# artik530_SOM.net
KiCad netlist of a schematic drawn in EAGLE
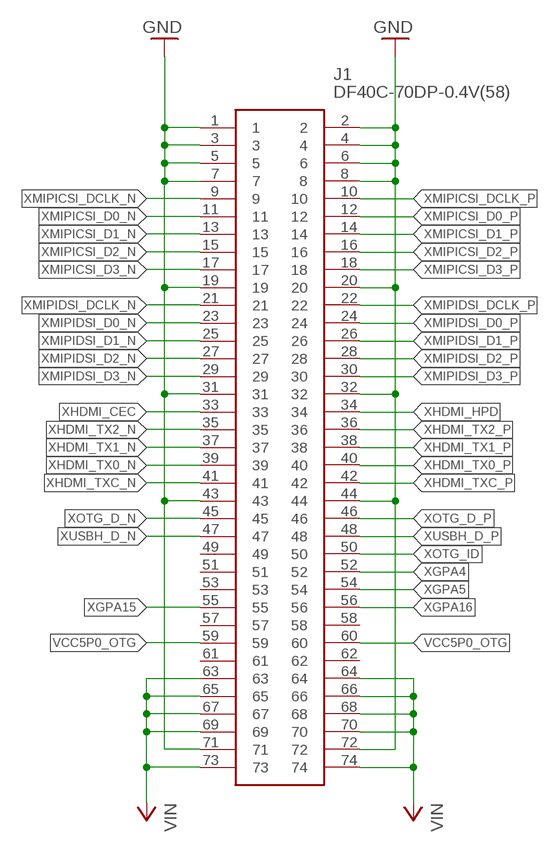
[diagram p0: schematic, sheet 1, part 1 of 2]
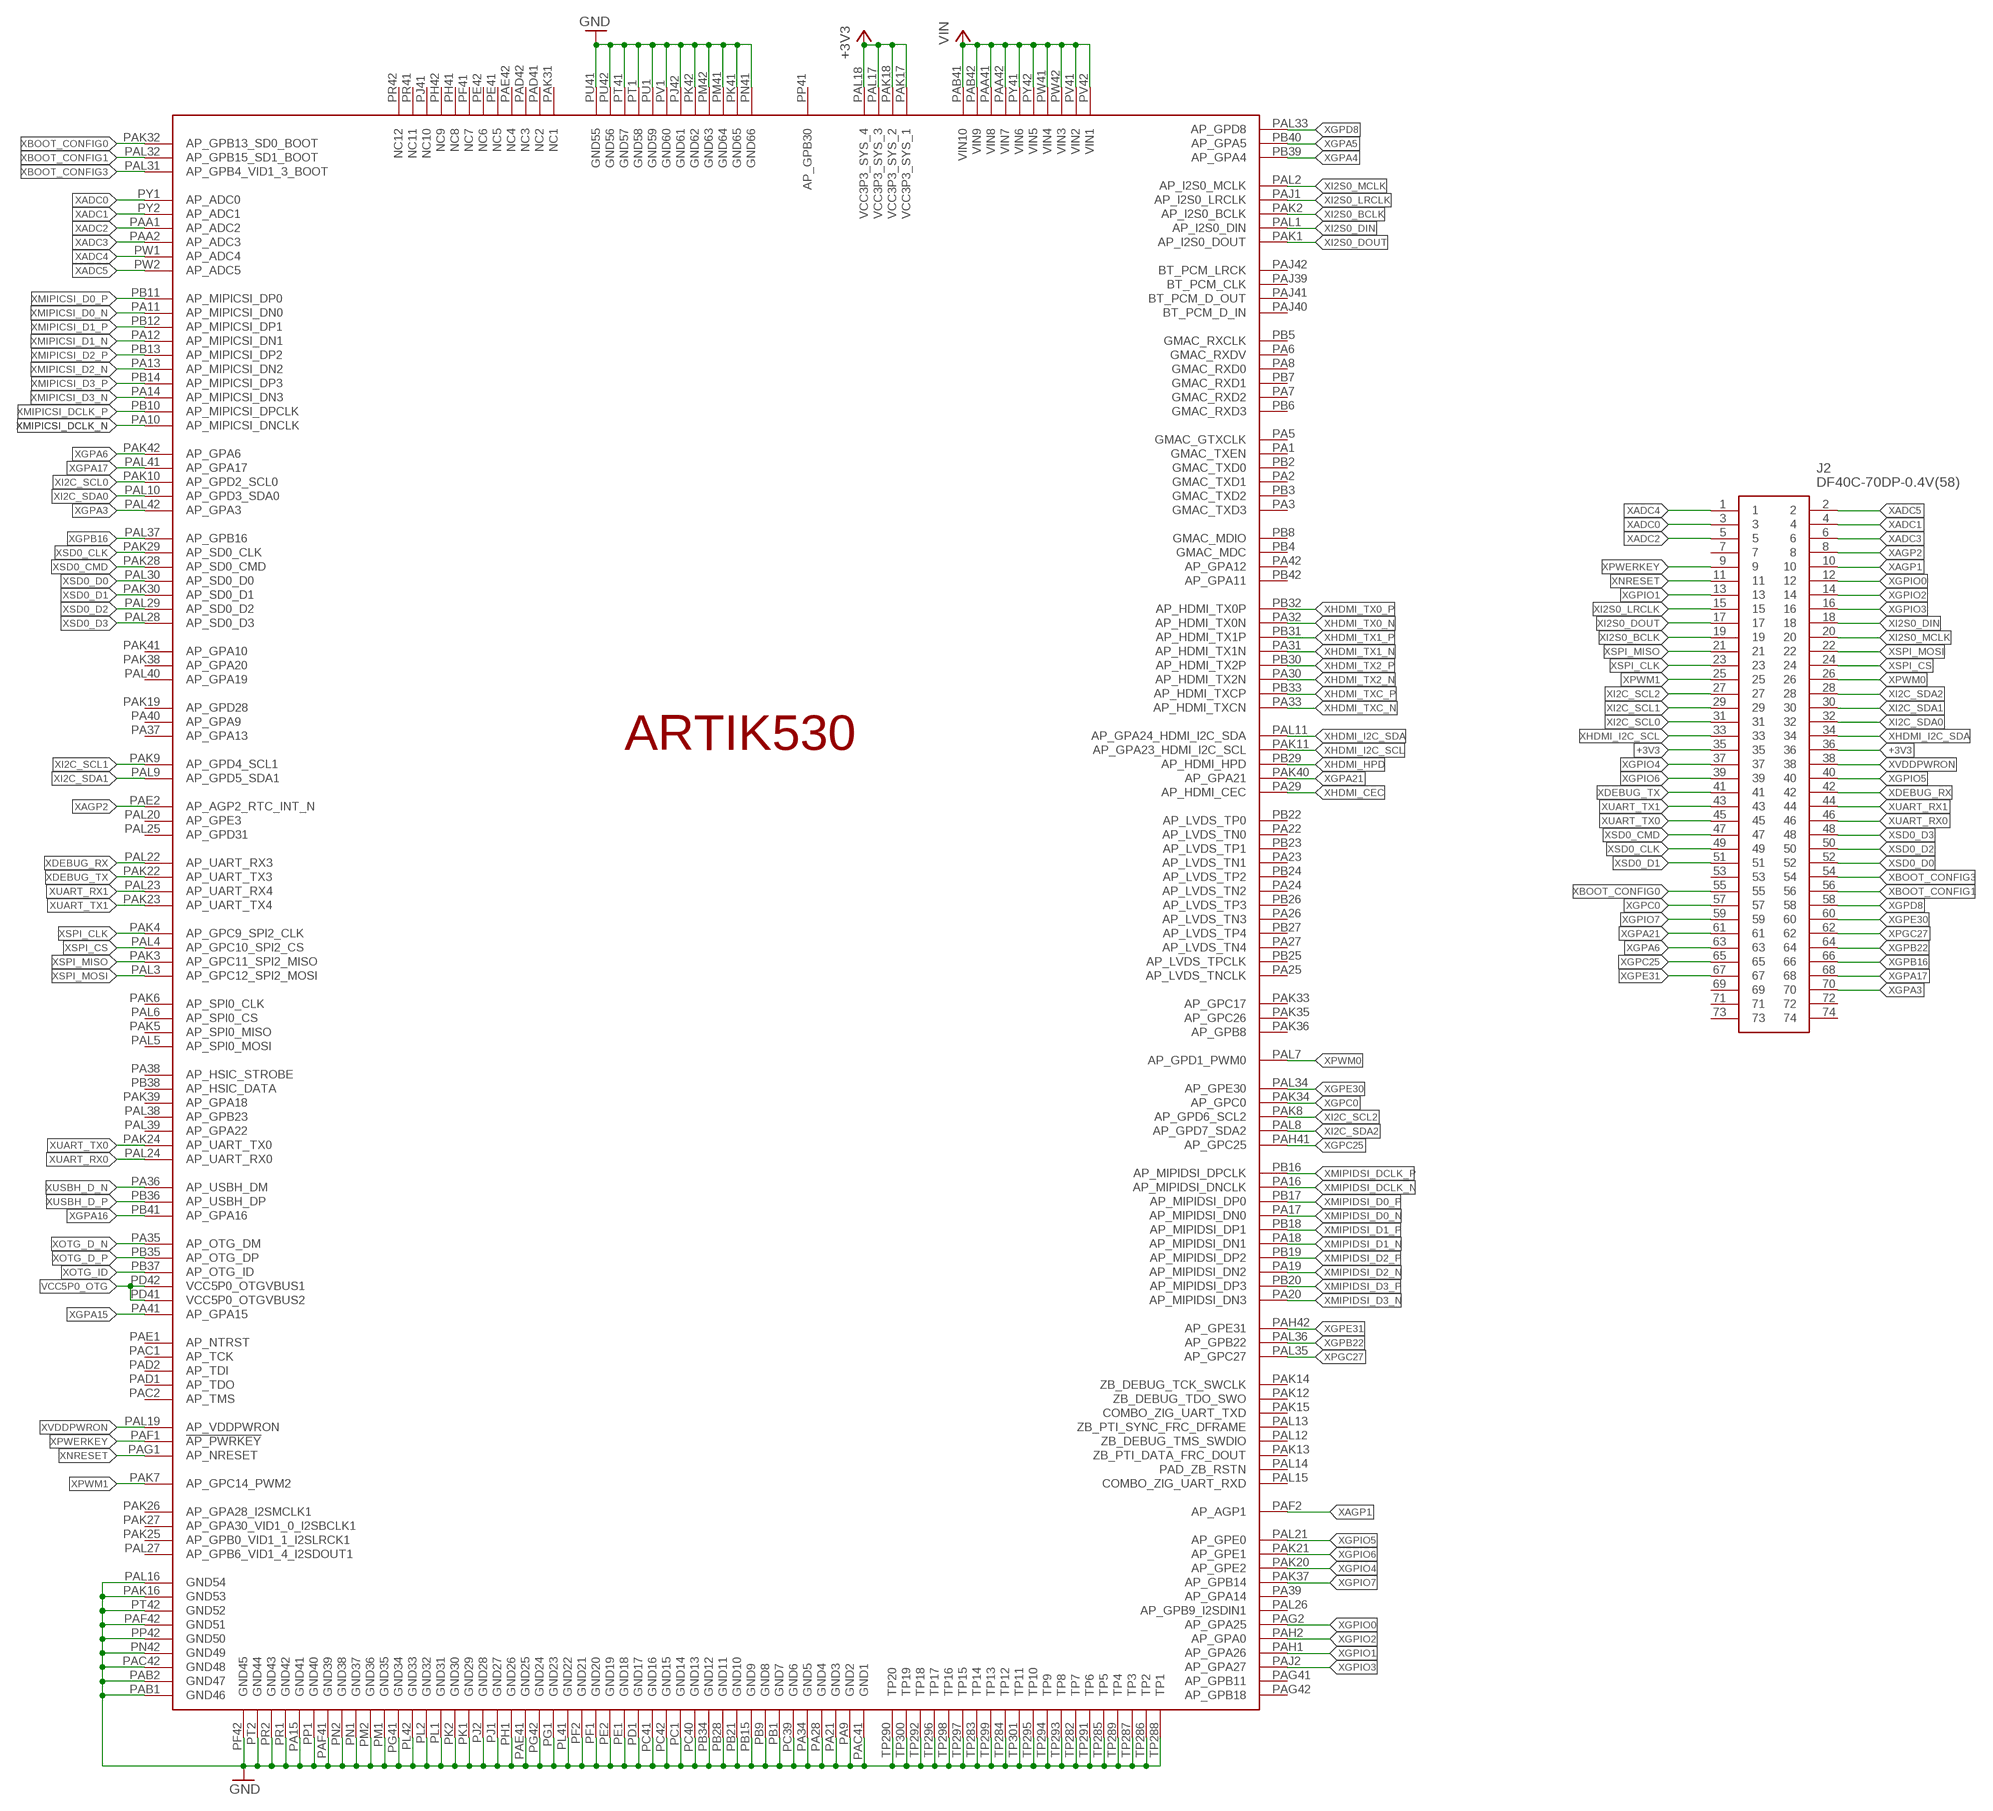
[diagram p1: schematic, sheet 1, part 2 of 2]

(export (version "E")
  (design (tool "Eeschema 10.0.6"))
  (components
    (comp (ref "J1")
      (value "DF40C-70DP-0.4V(58)")
      (footprint "eagle-import:DF40C70DP04V58")
      (fields
        (field (name "ARROW_PART_NUMBER") "DF40C-70DP-0.4V(51)")
        (field (name "RS_PART_NUMBER") "1664877")
      )
      (libsource (lib "eagle-import") (part "DF40C-70DP-0.4V(58)"))
    )
    (comp (ref "J2")
      (value "DF40C-70DP-0.4V(58)")
      (footprint "eagle-import:DF40C70DP04V58")
      (fields
        (field (name "ARROW_PART_NUMBER") "DF40C-70DP-0.4V(51)")
        (field (name "RS_PART_NUMBER") "1664877")
      )
      (libsource (lib "eagle-import") (part "DF40C-70DP-0.4V(58)"))
    )
    (comp (ref "U$1")
      (value "ARTIK530ARTIK530_SOM")
      (footprint "eagle-import:ARTIK5")
      (libsource (lib "eagle-import") (part "ARTIK530ARTIK530_SOM"))
    )
  )
  (nets
    (net (code "1") (name "+3V3") (class "Default")
      (node (ref "J2") (pin "35") (pinfunction "35_35") (pintype "bidirectional"))
      (node (ref "J2") (pin "36") (pinfunction "36_36") (pintype "bidirectional"))
      (node (ref "U$1") (pin "PAK17") (pinfunction "VCC3P3_SYS_1_PAK17") (pintype "bidirectional"))
      (node (ref "U$1") (pin "PAK18") (pinfunction "VCC3P3_SYS_2_PAK18") (pintype "bidirectional"))
      (node (ref "U$1") (pin "PAL17") (pinfunction "VCC3P3_SYS_3_PAL17") (pintype "bidirectional"))
      (node (ref "U$1") (pin "PAL18") (pinfunction "VCC3P3_SYS_4_PAL18") (pintype "bidirectional"))
    )
    (net (code "2") (name "GND") (class "Default")
      (node (ref "J1") (pin "1") (pinfunction "1_1") (pintype "bidirectional"))
      (node (ref "J1") (pin "19") (pinfunction "19_19") (pintype "bidirectional"))
      (node (ref "J1") (pin "2") (pinfunction "2_2") (pintype "bidirectional"))
      (node (ref "J1") (pin "20") (pinfunction "20_20") (pintype "bidirectional"))
      (node (ref "J1") (pin "3") (pinfunction "3_3") (pintype "bidirectional"))
      (node (ref "J1") (pin "31") (pinfunction "31_31") (pintype "bidirectional"))
      (node (ref "J1") (pin "32") (pinfunction "32_32") (pintype "bidirectional"))
      (node (ref "J1") (pin "4") (pinfunction "4_4") (pintype "bidirectional"))
      (node (ref "J1") (pin "43") (pinfunction "43_43") (pintype "bidirectional"))
      (node (ref "J1") (pin "44") (pinfunction "44_44") (pintype "bidirectional"))
      (node (ref "J1") (pin "5") (pinfunction "5_5") (pintype "bidirectional"))
      (node (ref "J1") (pin "6") (pinfunction "6_6") (pintype "bidirectional"))
      (node (ref "J1") (pin "7") (pinfunction "7_7") (pintype "bidirectional"))
      (node (ref "J1") (pin "71") (pinfunction "71_71") (pintype "bidirectional"))
      (node (ref "J1") (pin "72") (pinfunction "72_72") (pintype "bidirectional"))
      (node (ref "J1") (pin "8") (pinfunction "8_8") (pintype "bidirectional"))
      (node (ref "U$1") (pin "PA15") (pinfunction "GND41_PA15") (pintype "bidirectional"))
      (node (ref "U$1") (pin "PA21") (pinfunction "GND3_PA21") (pintype "bidirectional"))
      (node (ref "U$1") (pin "PA28") (pinfunction "GND4_PA28") (pintype "bidirectional"))
      (node (ref "U$1") (pin "PA34") (pinfunction "GND5_PA34") (pintype "bidirectional"))
      (node (ref "U$1") (pin "PA9") (pinfunction "GND2_PA9") (pintype "bidirectional"))
      (node (ref "U$1") (pin "PAB1") (pinfunction "GND46_PAB1") (pintype "bidirectional"))
      (node (ref "U$1") (pin "PAB2") (pinfunction "GND47_PAB2") (pintype "bidirectional"))
      (node (ref "U$1") (pin "PAC41") (pinfunction "GND1_PAC41") (pintype "bidirectional"))
      (node (ref "U$1") (pin "PAC42") (pinfunction "GND48_PAC42") (pintype "bidirectional"))
      (node (ref "U$1") (pin "PAE41") (pinfunction "GND25_PAE41") (pintype "bidirectional"))
      (node (ref "U$1") (pin "PAF41") (pinfunction "GND39_PAF41") (pintype "bidirectional"))
      (node (ref "U$1") (pin "PAF42") (pinfunction "GND51_PAF42") (pintype "bidirectional"))
      (node (ref "U$1") (pin "PAK16") (pinfunction "GND53_PAK16") (pintype "bidirectional"))
      (node (ref "U$1") (pin "PAL16") (pinfunction "GND54_PAL16") (pintype "bidirectional"))
      (node (ref "U$1") (pin "PB1") (pinfunction "GND7_PB1") (pintype "bidirectional"))
      (node (ref "U$1") (pin "PB15") (pinfunction "GND9_PB15") (pintype "bidirectional"))
      (node (ref "U$1") (pin "PB21") (pinfunction "GND10_PB21") (pintype "bidirectional"))
      (node (ref "U$1") (pin "PB28") (pinfunction "GND11_PB28") (pintype "bidirectional"))
      (node (ref "U$1") (pin "PB34") (pinfunction "GND12_PB34") (pintype "bidirectional"))
      (node (ref "U$1") (pin "PB9") (pinfunction "GND8_PB9") (pintype "bidirectional"))
      (node (ref "U$1") (pin "PC1") (pinfunction "GND14_PC1") (pintype "bidirectional"))
      (node (ref "U$1") (pin "PC39") (pinfunction "GND6_PC39") (pintype "bidirectional"))
      (node (ref "U$1") (pin "PC40") (pinfunction "GND13_PC40") (pintype "bidirectional"))
      (node (ref "U$1") (pin "PC41") (pinfunction "GND16_PC41") (pintype "bidirectional"))
      (node (ref "U$1") (pin "PC42") (pinfunction "GND15_PC42") (pintype "bidirectional"))
      (node (ref "U$1") (pin "PD1") (pinfunction "GND17_PD1") (pintype "bidirectional"))
      (node (ref "U$1") (pin "PE1") (pinfunction "GND18_PE1") (pintype "bidirectional"))
      (node (ref "U$1") (pin "PE2") (pinfunction "GND19_PE2") (pintype "bidirectional"))
      (node (ref "U$1") (pin "PF1") (pinfunction "GND20_PF1") (pintype "bidirectional"))
      (node (ref "U$1") (pin "PF2") (pinfunction "GND21_PF2") (pintype "bidirectional"))
      (node (ref "U$1") (pin "PF42") (pinfunction "GND45_PF42") (pintype "bidirectional"))
      (node (ref "U$1") (pin "PG1") (pinfunction "GND23_PG1") (pintype "bidirectional"))
      (node (ref "U$1") (pin "PG41") (pinfunction "GND34_PG41") (pintype "bidirectional"))
      (node (ref "U$1") (pin "PG42") (pinfunction "GND24_PG42") (pintype "bidirectional"))
      (node (ref "U$1") (pin "PH1") (pinfunction "GND26_PH1") (pintype "bidirectional"))
      (node (ref "U$1") (pin "PJ1") (pinfunction "GND27_PJ1") (pintype "bidirectional"))
      (node (ref "U$1") (pin "PJ2") (pinfunction "GND28_PJ2") (pintype "bidirectional"))
      (node (ref "U$1") (pin "PJ42") (pinfunction "GND61_PJ42") (pintype "bidirectional"))
      (node (ref "U$1") (pin "PK1") (pinfunction "GND29_PK1") (pintype "bidirectional"))
      (node (ref "U$1") (pin "PK2") (pinfunction "GND30_PK2") (pintype "bidirectional"))
      (node (ref "U$1") (pin "PK41") (pinfunction "GND65_PK41") (pintype "bidirectional"))
      (node (ref "U$1") (pin "PK42") (pinfunction "GND62_PK42") (pintype "bidirectional"))
      (node (ref "U$1") (pin "PL1") (pinfunction "GND31_PL1") (pintype "bidirectional"))
      (node (ref "U$1") (pin "PL2") (pinfunction "GND32_PL2") (pintype "bidirectional"))
      (node (ref "U$1") (pin "PL41") (pinfunction "GND22_PL41") (pintype "bidirectional"))
      (node (ref "U$1") (pin "PL42") (pinfunction "GND33_PL42") (pintype "bidirectional"))
      (node (ref "U$1") (pin "PM1") (pinfunction "GND35_PM1") (pintype "bidirectional"))
      (node (ref "U$1") (pin "PM2") (pinfunction "GND36_PM2") (pintype "bidirectional"))
      (node (ref "U$1") (pin "PM41") (pinfunction "GND64_PM41") (pintype "bidirectional"))
      (node (ref "U$1") (pin "PM42") (pinfunction "GND63_PM42") (pintype "bidirectional"))
      (node (ref "U$1") (pin "PN1") (pinfunction "GND37_PN1") (pintype "bidirectional"))
      (node (ref "U$1") (pin "PN2") (pinfunction "GND38_PN2") (pintype "bidirectional"))
      (node (ref "U$1") (pin "PN41") (pinfunction "GND66_PN41") (pintype "bidirectional"))
      (node (ref "U$1") (pin "PN42") (pinfunction "GND49_PN42") (pintype "bidirectional"))
      (node (ref "U$1") (pin "PP1") (pinfunction "GND40_PP1") (pintype "bidirectional"))
      (node (ref "U$1") (pin "PP42") (pinfunction "GND50_PP42") (pintype "bidirectional"))
      (node (ref "U$1") (pin "PR1") (pinfunction "GND42_PR1") (pintype "bidirectional"))
      (node (ref "U$1") (pin "PR2") (pinfunction "GND43_PR2") (pintype "bidirectional"))
      (node (ref "U$1") (pin "PT1") (pinfunction "GND58_PT1") (pintype "bidirectional"))
      (node (ref "U$1") (pin "PT2") (pinfunction "GND44_PT2") (pintype "bidirectional"))
      (node (ref "U$1") (pin "PT41") (pinfunction "GND57_PT41") (pintype "bidirectional"))
      (node (ref "U$1") (pin "PT42") (pinfunction "GND52_PT42") (pintype "bidirectional"))
      (node (ref "U$1") (pin "PU1") (pinfunction "GND59_PU1") (pintype "bidirectional"))
      (node (ref "U$1") (pin "PU41") (pinfunction "GND55_PU41") (pintype "bidirectional"))
      (node (ref "U$1") (pin "PU42") (pinfunction "GND56_PU42") (pintype "bidirectional"))
      (node (ref "U$1") (pin "PV1") (pinfunction "GND60_PV1") (pintype "bidirectional"))
      (node (ref "U$1") (pin "TP282") (pinfunction "TP7_TP282") (pintype "bidirectional"))
      (node (ref "U$1") (pin "TP283") (pinfunction "TP14_TP283") (pintype "bidirectional"))
      (node (ref "U$1") (pin "TP284") (pinfunction "TP12_TP284") (pintype "bidirectional"))
      (node (ref "U$1") (pin "TP285") (pinfunction "TP5_TP285") (pintype "bidirectional"))
      (node (ref "U$1") (pin "TP286") (pinfunction "TP2_TP286") (pintype "bidirectional"))
      (node (ref "U$1") (pin "TP287") (pinfunction "TP3_TP287") (pintype "bidirectional"))
      (node (ref "U$1") (pin "TP288") (pinfunction "TP1_TP288") (pintype "bidirectional"))
      (node (ref "U$1") (pin "TP289") (pinfunction "TP4_TP289") (pintype "bidirectional"))
      (node (ref "U$1") (pin "TP290") (pinfunction "TP20_TP290") (pintype "bidirectional"))
      (node (ref "U$1") (pin "TP291") (pinfunction "TP6_TP291") (pintype "bidirectional"))
      (node (ref "U$1") (pin "TP292") (pinfunction "TP18_TP292") (pintype "bidirectional"))
      (node (ref "U$1") (pin "TP293") (pinfunction "TP8_TP293") (pintype "bidirectional"))
      (node (ref "U$1") (pin "TP294") (pinfunction "TP9_TP294") (pintype "bidirectional"))
      (node (ref "U$1") (pin "TP295") (pinfunction "TP10_TP295") (pintype "bidirectional"))
      (node (ref "U$1") (pin "TP296") (pinfunction "TP17_TP296") (pintype "bidirectional"))
      (node (ref "U$1") (pin "TP297") (pinfunction "TP15_TP297") (pintype "bidirectional"))
      (node (ref "U$1") (pin "TP298") (pinfunction "TP16_TP298") (pintype "bidirectional"))
      (node (ref "U$1") (pin "TP299") (pinfunction "TP13_TP299") (pintype "bidirectional"))
      (node (ref "U$1") (pin "TP300") (pinfunction "TP19_TP300") (pintype "bidirectional"))
      (node (ref "U$1") (pin "TP301") (pinfunction "TP11_TP301") (pintype "bidirectional"))
    )
    (net (code "3") (name "VCC5P0_OTG") (class "Default")
      (node (ref "J1") (pin "59") (pinfunction "59_59") (pintype "bidirectional"))
      (node (ref "J1") (pin "60") (pinfunction "60_60") (pintype "bidirectional"))
      (node (ref "U$1") (pin "PD41") (pinfunction "VCC5P0_OTGVBUS2_PD41") (pintype "bidirectional"))
      (node (ref "U$1") (pin "PD42") (pinfunction "VCC5P0_OTGVBUS1_PD42") (pintype "bidirectional"))
    )
    (net (code "4") (name "VIN") (class "Default")
      (node (ref "J1") (pin "63") (pinfunction "63_63") (pintype "bidirectional"))
      (node (ref "J1") (pin "64") (pinfunction "64_64") (pintype "bidirectional"))
      (node (ref "J1") (pin "65") (pinfunction "65_65") (pintype "bidirectional"))
      (node (ref "J1") (pin "66") (pinfunction "66_66") (pintype "bidirectional"))
      (node (ref "J1") (pin "67") (pinfunction "67_67") (pintype "bidirectional"))
      (node (ref "J1") (pin "68") (pinfunction "68_68") (pintype "bidirectional"))
      (node (ref "J1") (pin "69") (pinfunction "69_69") (pintype "bidirectional"))
      (node (ref "J1") (pin "70") (pinfunction "70_70") (pintype "bidirectional"))
      (node (ref "J1") (pin "73") (pinfunction "73_73") (pintype "bidirectional"))
      (node (ref "J1") (pin "74") (pinfunction "74_74") (pintype "bidirectional"))
      (node (ref "U$1") (pin "PAA41") (pinfunction "VIN8_PAA41") (pintype "bidirectional"))
      (node (ref "U$1") (pin "PAA42") (pinfunction "VIN7_PAA42") (pintype "bidirectional"))
      (node (ref "U$1") (pin "PAB41") (pinfunction "VIN10_PAB41") (pintype "bidirectional"))
      (node (ref "U$1") (pin "PAB42") (pinfunction "VIN9_PAB42") (pintype "bidirectional"))
      (node (ref "U$1") (pin "PV41") (pinfunction "VIN2_PV41") (pintype "bidirectional"))
      (node (ref "U$1") (pin "PV42") (pinfunction "VIN1_PV42") (pintype "bidirectional"))
      (node (ref "U$1") (pin "PW41") (pinfunction "VIN4_PW41") (pintype "bidirectional"))
      (node (ref "U$1") (pin "PW42") (pinfunction "VIN3_PW42") (pintype "bidirectional"))
      (node (ref "U$1") (pin "PY41") (pinfunction "VIN6_PY41") (pintype "bidirectional"))
      (node (ref "U$1") (pin "PY42") (pinfunction "VIN5_PY42") (pintype "bidirectional"))
    )
    (net (code "5") (name "XADC0") (class "Default")
      (node (ref "J2") (pin "3") (pinfunction "3_3") (pintype "bidirectional"))
      (node (ref "U$1") (pin "PY1") (pinfunction "AP_ADC0_PY1") (pintype "bidirectional"))
    )
    (net (code "6") (name "XADC1") (class "Default")
      (node (ref "J2") (pin "4") (pinfunction "4_4") (pintype "bidirectional"))
      (node (ref "U$1") (pin "PY2") (pinfunction "AP_ADC1_PY2") (pintype "bidirectional"))
    )
    (net (code "7") (name "XADC2") (class "Default")
      (node (ref "J2") (pin "5") (pinfunction "5_5") (pintype "bidirectional"))
      (node (ref "U$1") (pin "PAA1") (pinfunction "AP_ADC2_PAA1") (pintype "bidirectional"))
    )
    (net (code "8") (name "XADC3") (class "Default")
      (node (ref "J2") (pin "6") (pinfunction "6_6") (pintype "bidirectional"))
      (node (ref "U$1") (pin "PAA2") (pinfunction "AP_ADC3_PAA2") (pintype "bidirectional"))
    )
    (net (code "9") (name "XADC4") (class "Default")
      (node (ref "J2") (pin "1") (pinfunction "1_1") (pintype "bidirectional"))
      (node (ref "U$1") (pin "PW1") (pinfunction "AP_ADC4_PW1") (pintype "bidirectional"))
    )
    (net (code "10") (name "XADC5") (class "Default")
      (node (ref "J2") (pin "2") (pinfunction "2_2") (pintype "bidirectional"))
      (node (ref "U$1") (pin "PW2") (pinfunction "AP_ADC5_PW2") (pintype "bidirectional"))
    )
    (net (code "11") (name "XAGP1") (class "Default")
      (node (ref "J2") (pin "10") (pinfunction "10_10") (pintype "bidirectional"))
      (node (ref "U$1") (pin "PAF2") (pinfunction "AP_AGP1_PAF2") (pintype "bidirectional"))
    )
    (net (code "12") (name "XAGP2") (class "Default")
      (node (ref "J2") (pin "8") (pinfunction "8_8") (pintype "bidirectional"))
      (node (ref "U$1") (pin "PAE2") (pinfunction "AP_AGP2_RTC_INT_N_PAE2") (pintype "bidirectional"))
    )
    (net (code "13") (name "XBOOT_CONFIG0") (class "Default")
      (node (ref "J2") (pin "55") (pinfunction "55_55") (pintype "bidirectional"))
      (node (ref "U$1") (pin "PAK32") (pinfunction "AP_GPB13_SD0_BOOT_PAK32") (pintype "bidirectional"))
    )
    (net (code "14") (name "XBOOT_CONFIG1") (class "Default")
      (node (ref "J2") (pin "56") (pinfunction "56_56") (pintype "bidirectional"))
      (node (ref "U$1") (pin "PAL32") (pinfunction "AP_GPB15_SD1_BOOT_PAL32") (pintype "bidirectional"))
    )
    (net (code "15") (name "XBOOT_CONFIG3") (class "Default")
      (node (ref "J2") (pin "54") (pinfunction "54_54") (pintype "bidirectional"))
      (node (ref "U$1") (pin "PAL31") (pinfunction "AP_GPB4_VID1_3_BOOT_PAL31") (pintype "bidirectional"))
    )
    (net (code "16") (name "XDEBUG_RX") (class "Default")
      (node (ref "J2") (pin "42") (pinfunction "42_42") (pintype "bidirectional"))
      (node (ref "U$1") (pin "PAL22") (pinfunction "AP_UART_RX3_PAL22") (pintype "bidirectional"))
    )
    (net (code "17") (name "XDEBUG_TX") (class "Default")
      (node (ref "J2") (pin "41") (pinfunction "41_41") (pintype "bidirectional"))
      (node (ref "U$1") (pin "PAK22") (pinfunction "AP_UART_TX3_PAK22") (pintype "bidirectional"))
    )
    (net (code "18") (name "XGPA3") (class "Default")
      (node (ref "J2") (pin "70") (pinfunction "70_70") (pintype "bidirectional"))
      (node (ref "U$1") (pin "PAL42") (pinfunction "AP_GPA3_PAL42") (pintype "bidirectional"))
    )
    (net (code "19") (name "XGPA4") (class "Default")
      (node (ref "J1") (pin "52") (pinfunction "52_52") (pintype "bidirectional"))
      (node (ref "U$1") (pin "PB39") (pinfunction "AP_GPA4_PB39") (pintype "bidirectional"))
    )
    (net (code "20") (name "XGPA5") (class "Default")
      (node (ref "J1") (pin "54") (pinfunction "54_54") (pintype "bidirectional"))
      (node (ref "U$1") (pin "PB40") (pinfunction "AP_GPA5_PB40") (pintype "bidirectional"))
    )
    (net (code "21") (name "XGPA6") (class "Default")
      (node (ref "J2") (pin "63") (pinfunction "63_63") (pintype "bidirectional"))
      (node (ref "U$1") (pin "PAK42") (pinfunction "AP_GPA6_PAK42") (pintype "bidirectional"))
    )
    (net (code "22") (name "XGPA15") (class "Default")
      (node (ref "J1") (pin "55") (pinfunction "55_55") (pintype "bidirectional"))
      (node (ref "U$1") (pin "PA41") (pinfunction "AP_GPA15_PA41") (pintype "bidirectional"))
    )
    (net (code "23") (name "XGPA16") (class "Default")
      (node (ref "J1") (pin "56") (pinfunction "56_56") (pintype "bidirectional"))
      (node (ref "U$1") (pin "PB41") (pinfunction "AP_GPA16_PB41") (pintype "bidirectional"))
    )
    (net (code "24") (name "XGPA17") (class "Default")
      (node (ref "J2") (pin "68") (pinfunction "68_68") (pintype "bidirectional"))
      (node (ref "U$1") (pin "PAL41") (pinfunction "AP_GPA17_PAL41") (pintype "bidirectional"))
    )
    (net (code "25") (name "XGPA21") (class "Default")
      (node (ref "J2") (pin "61") (pinfunction "61_61") (pintype "bidirectional"))
      (node (ref "U$1") (pin "PAK40") (pinfunction "AP_GPA21_PAK40") (pintype "bidirectional"))
    )
    (net (code "26") (name "XGPB16") (class "Default")
      (node (ref "J2") (pin "66") (pinfunction "66_66") (pintype "bidirectional"))
      (node (ref "U$1") (pin "PAL37") (pinfunction "AP_GPB16_PAL37") (pintype "bidirectional"))
    )
    (net (code "27") (name "XGPB22") (class "Default")
      (node (ref "J2") (pin "64") (pinfunction "64_64") (pintype "bidirectional"))
      (node (ref "U$1") (pin "PAL36") (pinfunction "AP_GPB22_PAL36") (pintype "bidirectional"))
    )
    (net (code "28") (name "XGPC0") (class "Default")
      (node (ref "J2") (pin "57") (pinfunction "57_57") (pintype "bidirectional"))
      (node (ref "U$1") (pin "PAK34") (pinfunction "AP_GPC0_PAK34") (pintype "bidirectional"))
    )
    (net (code "29") (name "XGPC25") (class "Default")
      (node (ref "J2") (pin "65") (pinfunction "65_65") (pintype "bidirectional"))
      (node (ref "U$1") (pin "PAH41") (pinfunction "AP_GPC25_PAH41") (pintype "bidirectional"))
    )
    (net (code "30") (name "XGPD8") (class "Default")
      (node (ref "J2") (pin "58") (pinfunction "58_58") (pintype "bidirectional"))
      (node (ref "U$1") (pin "PAL33") (pinfunction "AP_GPD8_PAL33") (pintype "bidirectional"))
    )
    (net (code "31") (name "XGPE30") (class "Default")
      (node (ref "J2") (pin "60") (pinfunction "60_60") (pintype "bidirectional"))
      (node (ref "U$1") (pin "PAL34") (pinfunction "AP_GPE30_PAL34") (pintype "bidirectional"))
    )
    (net (code "32") (name "XGPE31") (class "Default")
      (node (ref "J2") (pin "67") (pinfunction "67_67") (pintype "bidirectional"))
      (node (ref "U$1") (pin "PAH42") (pinfunction "AP_GPE31_PAH42") (pintype "bidirectional"))
    )
    (net (code "33") (name "XGPIO0") (class "Default")
      (node (ref "J2") (pin "12") (pinfunction "12_12") (pintype "bidirectional"))
      (node (ref "U$1") (pin "PAG2") (pinfunction "AP_GPA25_PAG2") (pintype "bidirectional"))
    )
    (net (code "34") (name "XGPIO1") (class "Default")
      (node (ref "J2") (pin "13") (pinfunction "13_13") (pintype "bidirectional"))
      (node (ref "U$1") (pin "PAH1") (pinfunction "AP_GPA26_PAH1") (pintype "bidirectional"))
    )
    (net (code "35") (name "XGPIO2") (class "Default")
      (node (ref "J2") (pin "14") (pinfunction "14_14") (pintype "bidirectional"))
      (node (ref "U$1") (pin "PAH2") (pinfunction "AP_GPA0_PAH2") (pintype "bidirectional"))
    )
    (net (code "36") (name "XGPIO3") (class "Default")
      (node (ref "J2") (pin "16") (pinfunction "16_16") (pintype "bidirectional"))
      (node (ref "U$1") (pin "PAJ2") (pinfunction "AP_GPA27_PAJ2") (pintype "bidirectional"))
    )
    (net (code "37") (name "XGPIO4") (class "Default")
      (node (ref "J2") (pin "37") (pinfunction "37_37") (pintype "bidirectional"))
      (node (ref "U$1") (pin "PAK20") (pinfunction "AP_GPE2_PAK20") (pintype "bidirectional"))
    )
    (net (code "38") (name "XGPIO5") (class "Default")
      (node (ref "J2") (pin "40") (pinfunction "40_40") (pintype "bidirectional"))
      (node (ref "U$1") (pin "PAL21") (pinfunction "AP_GPE0_PAL21") (pintype "bidirectional"))
    )
    (net (code "39") (name "XGPIO6") (class "Default")
      (node (ref "J2") (pin "39") (pinfunction "39_39") (pintype "bidirectional"))
      (node (ref "U$1") (pin "PAK21") (pinfunction "AP_GPE1_PAK21") (pintype "bidirectional"))
    )
    (net (code "40") (name "XGPIO7") (class "Default")
      (node (ref "J2") (pin "59") (pinfunction "59_59") (pintype "bidirectional"))
      (node (ref "U$1") (pin "PAK37") (pinfunction "AP_GPB14_PAK37") (pintype "bidirectional"))
    )
    (net (code "41") (name "XHDMI_CEC") (class "Default")
      (node (ref "J1") (pin "33") (pinfunction "33_33") (pintype "bidirectional"))
      (node (ref "U$1") (pin "PA29") (pinfunction "AP_HDMI_CEC_PA29") (pintype "bidirectional"))
    )
    (net (code "42") (name "XHDMI_HPD") (class "Default")
      (node (ref "J1") (pin "34") (pinfunction "34_34") (pintype "bidirectional"))
      (node (ref "U$1") (pin "PB29") (pinfunction "AP_HDMI_HPD_PB29") (pintype "bidirectional"))
    )
    (net (code "43") (name "XHDMI_I2C_SCL") (class "Default")
      (node (ref "J2") (pin "33") (pinfunction "33_33") (pintype "bidirectional"))
      (node (ref "U$1") (pin "PAK11") (pinfunction "AP_GPA23_HDMI_I2C_SCL_PAK11") (pintype "bidirectional"))
    )
    (net (code "44") (name "XHDMI_I2C_SDA") (class "Default")
      (node (ref "J2") (pin "34") (pinfunction "34_34") (pintype "bidirectional"))
      (node (ref "U$1") (pin "PAL11") (pinfunction "AP_GPA24_HDMI_I2C_SDA_PAL11") (pintype "bidirectional"))
    )
    (net (code "45") (name "XHDMI_TX0_N") (class "Default")
      (node (ref "J1") (pin "39") (pinfunction "39_39") (pintype "bidirectional"))
      (node (ref "U$1") (pin "PA32") (pinfunction "AP_HDMI_TX0N_PA32") (pintype "bidirectional"))
    )
    (net (code "46") (name "XHDMI_TX0_P") (class "Default")
      (node (ref "J1") (pin "40") (pinfunction "40_40") (pintype "bidirectional"))
      (node (ref "U$1") (pin "PB32") (pinfunction "AP_HDMI_TX0P_PB32") (pintype "bidirectional"))
    )
    (net (code "47") (name "XHDMI_TX1_N") (class "Default")
      (node (ref "J1") (pin "37") (pinfunction "37_37") (pintype "bidirectional"))
      (node (ref "U$1") (pin "PA31") (pinfunction "AP_HDMI_TX1N_PA31") (pintype "bidirectional"))
    )
    (net (code "48") (name "XHDMI_TX1_P") (class "Default")
      (node (ref "J1") (pin "38") (pinfunction "38_38") (pintype "bidirectional"))
      (node (ref "U$1") (pin "PB31") (pinfunction "AP_HDMI_TX1P_PB31") (pintype "bidirectional"))
    )
    (net (code "49") (name "XHDMI_TX2_N") (class "Default")
      (node (ref "J1") (pin "35") (pinfunction "35_35") (pintype "bidirectional"))
      (node (ref "U$1") (pin "PA30") (pinfunction "AP_HDMI_TX2N_PA30") (pintype "bidirectional"))
    )
    (net (code "50") (name "XHDMI_TX2_P") (class "Default")
      (node (ref "J1") (pin "36") (pinfunction "36_36") (pintype "bidirectional"))
      (node (ref "U$1") (pin "PB30") (pinfunction "AP_HDMI_TX2P_PB30") (pintype "bidirectional"))
    )
    (net (code "51") (name "XHDMI_TXC_N") (class "Default")
      (node (ref "J1") (pin "41") (pinfunction "41_41") (pintype "bidirectional"))
      (node (ref "U$1") (pin "PA33") (pinfunction "AP_HDMI_TXCN_PA33") (pintype "bidirectional"))
    )
    (net (code "52") (name "XHDMI_TXC_P") (class "Default")
      (node (ref "J1") (pin "42") (pinfunction "42_42") (pintype "bidirectional"))
      (node (ref "U$1") (pin "PB33") (pinfunction "AP_HDMI_TXCP_PB33") (pintype "bidirectional"))
    )
    (net (code "53") (name "XI2C_SCL0") (class "Default")
      (node (ref "J2") (pin "31") (pinfunction "31_31") (pintype "bidirectional"))
      (node (ref "U$1") (pin "PAK10") (pinfunction "AP_GPD2_SCL0_PAK10") (pintype "bidirectional"))
    )
    (net (code "54") (name "XI2C_SCL1") (class "Default")
      (node (ref "J2") (pin "29") (pinfunction "29_29") (pintype "bidirectional"))
      (node (ref "U$1") (pin "PAK9") (pinfunction "AP_GPD4_SCL1_PAK9") (pintype "bidirectional"))
    )
    (net (code "55") (name "XI2C_SCL2") (class "Default")
      (node (ref "J2") (pin "27") (pinfunction "27_27") (pintype "bidirectional"))
      (node (ref "U$1") (pin "PAK8") (pinfunction "AP_GPD6_SCL2_PAK8") (pintype "bidirectional"))
    )
    (net (code "56") (name "XI2C_SDA0") (class "Default")
      (node (ref "J2") (pin "32") (pinfunction "32_32") (pintype "bidirectional"))
      (node (ref "U$1") (pin "PAL10") (pinfunction "AP_GPD3_SDA0_PAL10") (pintype "bidirectional"))
    )
    (net (code "57") (name "XI2C_SDA1") (class "Default")
      (node (ref "J2") (pin "30") (pinfunction "30_30") (pintype "bidirectional"))
      (node (ref "U$1") (pin "PAL9") (pinfunction "AP_GPD5_SDA1_PAL9") (pintype "bidirectional"))
    )
    (net (code "58") (name "XI2C_SDA2") (class "Default")
      (node (ref "J2") (pin "28") (pinfunction "28_28") (pintype "bidirectional"))
      (node (ref "U$1") (pin "PAL8") (pinfunction "AP_GPD7_SDA2_PAL8") (pintype "bidirectional"))
    )
    (net (code "59") (name "XI2S0_BCLK") (class "Default")
      (node (ref "J2") (pin "19") (pinfunction "19_19") (pintype "bidirectional"))
      (node (ref "U$1") (pin "PAK2") (pinfunction "AP_I2S0_BCLK_PAK2") (pintype "bidirectional"))
    )
    (net (code "60") (name "XI2S0_DIN") (class "Default")
      (node (ref "J2") (pin "18") (pinfunction "18_18") (pintype "bidirectional"))
      (node (ref "U$1") (pin "PAL1") (pinfunction "AP_I2S0_DIN_PAL1") (pintype "bidirectional"))
    )
    (net (code "61") (name "XI2S0_DOUT") (class "Default")
      (node (ref "J2") (pin "17") (pinfunction "17_17") (pintype "bidirectional"))
      (node (ref "U$1") (pin "PAK1") (pinfunction "AP_I2S0_DOUT_PAK1") (pintype "bidirectional"))
    )
    (net (code "62") (name "XI2S0_LRCLK") (class "Default")
      (node (ref "J2") (pin "15") (pinfunction "15_15") (pintype "bidirectional"))
      (node (ref "U$1") (pin "PAJ1") (pinfunction "AP_I2S0_LRCLK_PAJ1") (pintype "bidirectional"))
    )
    (net (code "63") (name "XI2S0_MCLK") (class "Default")
      (node (ref "J2") (pin "20") (pinfunction "20_20") (pintype "bidirectional"))
      (node (ref "U$1") (pin "PAL2") (pinfunction "AP_I2S0_MCLK_PAL2") (pintype "bidirectional"))
    )
    (net (code "64") (name "XMIPICSI_D0_N") (class "Default")
      (node (ref "J1") (pin "11") (pinfunction "11_11") (pintype "bidirectional"))
      (node (ref "U$1") (pin "PA11") (pinfunction "AP_MIPICSI_DN0_PA11") (pintype "bidirectional"))
    )
    (net (code "65") (name "XMIPICSI_D0_P") (class "Default")
      (node (ref "J1") (pin "12") (pinfunction "12_12") (pintype "bidirectional"))
      (node (ref "U$1") (pin "PB11") (pinfunction "AP_MIPICSI_DP0_PB11") (pintype "bidirectional"))
    )
    (net (code "66") (name "XMIPICSI_D1_N") (class "Default")
      (node (ref "J1") (pin "13") (pinfunction "13_13") (pintype "bidirectional"))
      (node (ref "U$1") (pin "PA12") (pinfunction "AP_MIPICSI_DN1_PA12") (pintype "bidirectional"))
    )
    (net (code "67") (name "XMIPICSI_D1_P") (class "Default")
      (node (ref "J1") (pin "14") (pinfunction "14_14") (pintype "bidirectional"))
      (node (ref "U$1") (pin "PB12") (pinfunction "AP_MIPICSI_DP1_PB12") (pintype "bidirectional"))
    )
    (net (code "68") (name "XMIPICSI_D2_N") (class "Default")
      (node (ref "J1") (pin "15") (pinfunction "15_15") (pintype "bidirectional"))
      (node (ref "U$1") (pin "PA13") (pinfunction "AP_MIPICSI_DN2_PA13") (pintype "bidirectional"))
    )
    (net (code "69") (name "XMIPICSI_D2_P") (class "Default")
      (node (ref "J1") (pin "16") (pinfunction "16_16") (pintype "bidirectional"))
      (node (ref "U$1") (pin "PB13") (pinfunction "AP_MIPICSI_DP2_PB13") (pintype "bidirectional"))
    )
    (net (code "70") (name "XMIPICSI_D3_N") (class "Default")
      (node (ref "J1") (pin "17") (pinfunction "17_17") (pintype "bidirectional"))
      (node (ref "U$1") (pin "PA14") (pinfunction "AP_MIPICSI_DN3_PA14") (pintype "bidirectional"))
    )
    (net (code "71") (name "XMIPICSI_D3_P") (class "Default")
      (node (ref "J1") (pin "18") (pinfunction "18_18") (pintype "bidirectional"))
      (node (ref "U$1") (pin "PB14") (pinfunction "AP_MIPICSI_DP3_PB14") (pintype "bidirectional"))
    )
    (net (code "72") (name "XMIPICSI_DCLK_N") (class "Default")
      (node (ref "J1") (pin "9") (pinfunction "9_9") (pintype "bidirectional"))
      (node (ref "U$1") (pin "PA10") (pinfunction "AP_MIPICSI_DNCLK_PA10") (pintype "bidirectional"))
    )
    (net (code "73") (name "XMIPICSI_DCLK_P") (class "Default")
      (node (ref "J1") (pin "10") (pinfunction "10_10") (pintype "bidirectional"))
      (node (ref "U$1") (pin "PB10") (pinfunction "AP_MIPICSI_DPCLK_PB10") (pintype "bidirectional"))
    )
    (net (code "74") (name "XMIPIDSI_D0_N") (class "Default")
      (node (ref "J1") (pin "23") (pinfunction "23_23") (pintype "bidirectional"))
      (node (ref "U$1") (pin "PA17") (pinfunction "AP_MIPIDSI_DN0_PA17") (pintype "bidirectional"))
    )
    (net (code "75") (name "XMIPIDSI_D0_P") (class "Default")
      (node (ref "J1") (pin "24") (pinfunction "24_24") (pintype "bidirectional"))
      (node (ref "U$1") (pin "PB17") (pinfunction "AP_MIPIDSI_DP0_PB17") (pintype "bidirectional"))
    )
    (net (code "76") (name "XMIPIDSI_D1_N") (class "Default")
      (node (ref "J1") (pin "25") (pinfunction "25_25") (pintype "bidirectional"))
      (node (ref "U$1") (pin "PA18") (pinfunction "AP_MIPIDSI_DN1_PA18") (pintype "bidirectional"))
    )
    (net (code "77") (name "XMIPIDSI_D1_P") (class "Default")
      (node (ref "J1") (pin "26") (pinfunction "26_26") (pintype "bidirectional"))
      (node (ref "U$1") (pin "PB18") (pinfunction "AP_MIPIDSI_DP1_PB18") (pintype "bidirectional"))
    )
    (net (code "78") (name "XMIPIDSI_D2_N") (class "Default")
      (node (ref "J1") (pin "27") (pinfunction "27_27") (pintype "bidirectional"))
      (node (ref "U$1") (pin "PA19") (pinfunction "AP_MIPIDSI_DN2_PA19") (pintype "bidirectional"))
    )
    (net (code "79") (name "XMIPIDSI_D2_P") (class "Default")
      (node (ref "J1") (pin "28") (pinfunction "28_28") (pintype "bidirectional"))
      (node (ref "U$1") (pin "PB19") (pinfunction "AP_MIPIDSI_DP2_PB19") (pintype "bidirectional"))
    )
    (net (code "80") (name "XMIPIDSI_D3_N") (class "Default")
      (node (ref "J1") (pin "29") (pinfunction "29_29") (pintype "bidirectional"))
      (node (ref "U$1") (pin "PA20") (pinfunction "AP_MIPIDSI_DN3_PA20") (pintype "bidirectional"))
    )
    (net (code "81") (name "XMIPIDSI_D3_P") (class "Default")
      (node (ref "J1") (pin "30") (pinfunction "30_30") (pintype "bidirectional"))
      (node (ref "U$1") (pin "PB20") (pinfunction "AP_MIPIDSI_DP3_PB20") (pintype "bidirectional"))
    )
    (net (code "82") (name "XMIPIDSI_DCLK_N") (class "Default")
      (node (ref "J1") (pin "21") (pinfunction "21_21") (pintype "bidirectional"))
      (node (ref "U$1") (pin "PA16") (pinfunction "AP_MIPIDSI_DNCLK_PA16") (pintype "bidirectional"))
    )
    (net (code "83") (name "XMIPIDSI_DCLK_P") (class "Default")
      (node (ref "J1") (pin "22") (pinfunction "22_22") (pintype "bidirectional"))
      (node (ref "U$1") (pin "PB16") (pinfunction "AP_MIPIDSI_DPCLK_PB16") (pintype "bidirectional"))
    )
    (net (code "84") (name "XNRESET") (class "Default")
      (node (ref "J2") (pin "11") (pinfunction "11_11") (pintype "bidirectional"))
      (node (ref "U$1") (pin "PAG1") (pinfunction "AP_NRESET_PAG1") (pintype "bidirectional"))
    )
    (net (code "85") (name "XOTG_D_N") (class "Default")
      (node (ref "J1") (pin "45") (pinfunction "45_45") (pintype "bidirectional"))
      (node (ref "U$1") (pin "PA35") (pinfunction "AP_OTG_DM_PA35") (pintype "bidirectional"))
    )
    (net (code "86") (name "XOTG_D_P") (class "Default")
      (node (ref "J1") (pin "46") (pinfunction "46_46") (pintype "bidirectional"))
      (node (ref "U$1") (pin "PB35") (pinfunction "AP_OTG_DP_PB35") (pintype "bidirectional"))
    )
    (net (code "87") (name "XOTG_ID") (class "Default")
      (node (ref "J1") (pin "50") (pinfunction "50_50") (pintype "bidirectional"))
      (node (ref "U$1") (pin "PB37") (pinfunction "AP_OTG_ID_PB37") (pintype "bidirectional"))
    )
    (net (code "88") (name "XPGC27") (class "Default")
      (node (ref "J2") (pin "62") (pinfunction "62_62") (pintype "bidirectional"))
      (node (ref "U$1") (pin "PAL35") (pinfunction "AP_GPC27_PAL35") (pintype "bidirectional"))
    )
    (net (code "89") (name "XPWERKEY") (class "Default")
      (node (ref "J2") (pin "9") (pinfunction "9_9") (pintype "bidirectional"))
      (node (ref "U$1") (pin "PAF1") (pinfunction "~{AP_PWRKEY}_PAF1") (pintype "bidirectional"))
    )
    (net (code "90") (name "XPWM0") (class "Default")
      (node (ref "J2") (pin "26") (pinfunction "26_26") (pintype "bidirectional"))
      (node (ref "U$1") (pin "PAL7") (pinfunction "AP_GPD1_PWM0_PAL7") (pintype "bidirectional"))
    )
    (net (code "91") (name "XPWM1") (class "Default")
      (node (ref "J2") (pin "25") (pinfunction "25_25") (pintype "bidirectional"))
      (node (ref "U$1") (pin "PAK7") (pinfunction "AP_GPC14_PWM2_PAK7") (pintype "bidirectional"))
    )
    (net (code "92") (name "XSD0_CLK") (class "Default")
      (node (ref "J2") (pin "49") (pinfunction "49_49") (pintype "bidirectional"))
      (node (ref "U$1") (pin "PAK29") (pinfunction "AP_SD0_CLK_PAK29") (pintype "bidirectional"))
    )
    (net (code "93") (name "XSD0_CMD") (class "Default")
      (node (ref "J2") (pin "47") (pinfunction "47_47") (pintype "bidirectional"))
      (node (ref "U$1") (pin "PAK28") (pinfunction "AP_SD0_CMD_PAK28") (pintype "bidirectional"))
    )
    (net (code "94") (name "XSD0_D0") (class "Default")
      (node (ref "J2") (pin "52") (pinfunction "52_52") (pintype "bidirectional"))
      (node (ref "U$1") (pin "PAL30") (pinfunction "AP_SD0_D0_PAL30") (pintype "bidirectional"))
    )
    (net (code "95") (name "XSD0_D1") (class "Default")
      (node (ref "J2") (pin "51") (pinfunction "51_51") (pintype "bidirectional"))
      (node (ref "U$1") (pin "PAK30") (pinfunction "AP_SD0_D1_PAK30") (pintype "bidirectional"))
    )
    (net (code "96") (name "XSD0_D2") (class "Default")
      (node (ref "J2") (pin "50") (pinfunction "50_50") (pintype "bidirectional"))
      (node (ref "U$1") (pin "PAL29") (pinfunction "AP_SD0_D2_PAL29") (pintype "bidirectional"))
    )
    (net (code "97") (name "XSD0_D3") (class "Default")
      (node (ref "J2") (pin "48") (pinfunction "48_48") (pintype "bidirectional"))
      (node (ref "U$1") (pin "PAL28") (pinfunction "AP_SD0_D3_PAL28") (pintype "bidirectional"))
    )
    (net (code "98") (name "XSPI_CLK") (class "Default")
      (node (ref "J2") (pin "23") (pinfunction "23_23") (pintype "bidirectional"))
      (node (ref "U$1") (pin "PAK4") (pinfunction "AP_GPC9_SPI2_CLK_PAK4") (pintype "bidirectional"))
    )
    (net (code "99") (name "XSPI_CS") (class "Default")
      (node (ref "J2") (pin "24") (pinfunction "24_24") (pintype "bidirectional"))
      (node (ref "U$1") (pin "PAL4") (pinfunction "AP_GPC10_SPI2_CS_PAL4") (pintype "bidirectional"))
    )
    (net (code "100") (name "XSPI_MISO") (class "Default")
      (node (ref "J2") (pin "21") (pinfunction "21_21") (pintype "bidirectional"))
      (node (ref "U$1") (pin "PAK3") (pinfunction "AP_GPC11_SPI2_MISO_PAK3") (pintype "bidirectional"))
    )
    (net (code "101") (name "XSPI_MOSI") (class "Default")
      (node (ref "J2") (pin "22") (pinfunction "22_22") (pintype "bidirectional"))
      (node (ref "U$1") (pin "PAL3") (pinfunction "AP_GPC12_SPI2_MOSI_PAL3") (pintype "bidirectional"))
    )
    (net (code "102") (name "XUART_RX0") (class "Default")
      (node (ref "J2") (pin "46") (pinfunction "46_46") (pintype "bidirectional"))
      (node (ref "U$1") (pin "PAL24") (pinfunction "AP_UART_RX0_PAL24") (pintype "bidirectional"))
    )
    (net (code "103") (name "XUART_RX1") (class "Default")
      (node (ref "J2") (pin "44") (pinfunction "44_44") (pintype "bidirectional"))
      (node (ref "U$1") (pin "PAL23") (pinfunction "AP_UART_RX4_PAL23") (pintype "bidirectional"))
    )
    (net (code "104") (name "XUART_TX0") (class "Default")
      (node (ref "J2") (pin "45") (pinfunction "45_45") (pintype "bidirectional"))
      (node (ref "U$1") (pin "PAK24") (pinfunction "AP_UART_TX0_PAK24") (pintype "bidirectional"))
    )
    (net (code "105") (name "XUART_TX1") (class "Default")
      (node (ref "J2") (pin "43") (pinfunction "43_43") (pintype "bidirectional"))
      (node (ref "U$1") (pin "PAK23") (pinfunction "AP_UART_TX4_PAK23") (pintype "bidirectional"))
    )
    (net (code "106") (name "XUSBH_D_N") (class "Default")
      (node (ref "J1") (pin "47") (pinfunction "47_47") (pintype "bidirectional"))
      (node (ref "U$1") (pin "PA36") (pinfunction "AP_USBH_DM_PA36") (pintype "bidirectional"))
    )
    (net (code "107") (name "XUSBH_D_P") (class "Default")
      (node (ref "J1") (pin "48") (pinfunction "48_48") (pintype "bidirectional"))
      (node (ref "U$1") (pin "PB36") (pinfunction "AP_USBH_DP_PB36") (pintype "bidirectional"))
    )
    (net (code "108") (name "XVDDPWRON") (class "Default")
      (node (ref "J2") (pin "38") (pinfunction "38_38") (pintype "bidirectional"))
      (node (ref "U$1") (pin "PAL19") (pinfunction "AP_VDDPWRON_PAL19") (pintype "bidirectional"))
    )
    (net (code "109") (name "unconnected-(J1-Pad49)") (class "Default")
      (node (ref "J1") (pin "49") (pinfunction "49_49") (pintype "bidirectional"))
    )
    (net (code "110") (name "unconnected-(J1-Pad51)") (class "Default")
      (node (ref "J1") (pin "51") (pinfunction "51_51") (pintype "bidirectional"))
    )
    (net (code "111") (name "unconnected-(J1-Pad53)") (class "Default")
      (node (ref "J1") (pin "53") (pinfunction "53_53") (pintype "bidirectional"))
    )
    (net (code "112") (name "unconnected-(J1-Pad57)") (class "Default")
      (node (ref "J1") (pin "57") (pinfunction "57_57") (pintype "bidirectional"))
    )
    (net (code "113") (name "unconnected-(J1-Pad58)") (class "Default")
      (node (ref "J1") (pin "58") (pinfunction "58_58") (pintype "bidirectional"))
    )
    (net (code "114") (name "unconnected-(J1-Pad61)") (class "Default")
      (node (ref "J1") (pin "61") (pinfunction "61_61") (pintype "bidirectional"))
    )
    (net (code "115") (name "unconnected-(J1-Pad62)") (class "Default")
      (node (ref "J1") (pin "62") (pinfunction "62_62") (pintype "bidirectional"))
    )
    (net (code "116") (name "unconnected-(J2-Pad7)") (class "Default")
      (node (ref "J2") (pin "7") (pinfunction "7_7") (pintype "bidirectional"))
    )
    (net (code "117") (name "unconnected-(J2-Pad53)") (class "Default")
      (node (ref "J2") (pin "53") (pinfunction "53_53") (pintype "bidirectional"))
    )
    (net (code "118") (name "unconnected-(J2-Pad69)") (class "Default")
      (node (ref "J2") (pin "69") (pinfunction "69_69") (pintype "bidirectional"))
    )
    (net (code "119") (name "unconnected-(J2-Pad71)") (class "Default")
      (node (ref "J2") (pin "71") (pinfunction "71_71") (pintype "bidirectional"))
    )
    (net (code "120") (name "unconnected-(J2-Pad72)") (class "Default")
      (node (ref "J2") (pin "72") (pinfunction "72_72") (pintype "bidirectional"))
    )
    (net (code "121") (name "unconnected-(J2-Pad73)") (class "Default")
      (node (ref "J2") (pin "73") (pinfunction "73_73") (pintype "bidirectional"))
    )
    (net (code "122") (name "unconnected-(J2-Pad74)") (class "Default")
      (node (ref "J2") (pin "74") (pinfunction "74_74") (pintype "bidirectional"))
    )
    (net (code "123") (name "unconnected-(U$1-AP_GPA9-PadPA40)") (class "Default")
      (node (ref "U$1") (pin "PA40") (pinfunction "AP_GPA9_PA40") (pintype "bidirectional"))
    )
    (net (code "124") (name "unconnected-(U$1-AP_GPA10-PadPAK41)") (class "Default")
      (node (ref "U$1") (pin "PAK41") (pinfunction "AP_GPA10_PAK41") (pintype "bidirectional"))
    )
    (net (code "125") (name "unconnected-(U$1-AP_GPA11-PadPB42)") (class "Default")
      (node (ref "U$1") (pin "PB42") (pinfunction "AP_GPA11_PB42") (pintype "bidirectional"))
    )
    (net (code "126") (name "unconnected-(U$1-AP_GPA12-PadPA42)") (class "Default")
      (node (ref "U$1") (pin "PA42") (pinfunction "AP_GPA12_PA42") (pintype "bidirectional"))
    )
    (net (code "127") (name "unconnected-(U$1-AP_GPA13-PadPA37)") (class "Default")
      (node (ref "U$1") (pin "PA37") (pinfunction "AP_GPA13_PA37") (pintype "bidirectional"))
    )
    (net (code "128") (name "unconnected-(U$1-AP_GPA14-PadPA39)") (class "Default")
      (node (ref "U$1") (pin "PA39") (pinfunction "AP_GPA14_PA39") (pintype "bidirectional"))
    )
    (net (code "129") (name "unconnected-(U$1-AP_GPA18-PadPAK39)") (class "Default")
      (node (ref "U$1") (pin "PAK39") (pinfunction "AP_GPA18_PAK39") (pintype "bidirectional"))
    )
    (net (code "130") (name "unconnected-(U$1-AP_GPA19-PadPAL40)") (class "Default")
      (node (ref "U$1") (pin "PAL40") (pinfunction "AP_GPA19_PAL40") (pintype "bidirectional"))
    )
    (net (code "131") (name "unconnected-(U$1-AP_GPA20-PadPAK38)") (class "Default")
      (node (ref "U$1") (pin "PAK38") (pinfunction "AP_GPA20_PAK38") (pintype "bidirectional"))
    )
    (net (code "132") (name "unconnected-(U$1-AP_GPA22-PadPAL39)") (class "Default")
      (node (ref "U$1") (pin "PAL39") (pinfunction "AP_GPA22_PAL39") (pintype "bidirectional"))
    )
    (net (code "133") (name "unconnected-(U$1-AP_GPA28_I2SMCLK1-PadPAK26)") (class "Default")
      (node (ref "U$1") (pin "PAK26") (pinfunction "AP_GPA28_I2SMCLK1_PAK26") (pintype "bidirectional"))
    )
    (net (code "134") (name "unconnected-(U$1-AP_GPA30_VID1_0_I2SBCLK1-PadPAK27)") (class "Default")
      (node (ref "U$1") (pin "PAK27") (pinfunction "AP_GPA30_VID1_0_I2SBCLK1_PAK27") (pintype "bidirectional"))
    )
    (net (code "135") (name "unconnected-(U$1-AP_GPB0_VID1_1_I2SLRCK1-PadPAK25)") (class "Default")
      (node (ref "U$1") (pin "PAK25") (pinfunction "AP_GPB0_VID1_1_I2SLRCK1_PAK25") (pintype "bidirectional"))
    )
    (net (code "136") (name "unconnected-(U$1-AP_GPB6_VID1_4_I2SDOUT1-PadPAL27)") (class "Default")
      (node (ref "U$1") (pin "PAL27") (pinfunction "AP_GPB6_VID1_4_I2SDOUT1_PAL27") (pintype "bidirectional"))
    )
    (net (code "137") (name "unconnected-(U$1-AP_GPB8-PadPAK36)") (class "Default")
      (node (ref "U$1") (pin "PAK36") (pinfunction "AP_GPB8_PAK36") (pintype "bidirectional"))
    )
    (net (code "138") (name "unconnected-(U$1-AP_GPB9_I2SDIN1-PadPAL26)") (class "Default")
      (node (ref "U$1") (pin "PAL26") (pinfunction "AP_GPB9_I2SDIN1_PAL26") (pintype "bidirectional"))
    )
    (net (code "139") (name "unconnected-(U$1-AP_GPB11-PadPAG41)") (class "Default")
      (node (ref "U$1") (pin "PAG41") (pinfunction "AP_GPB11_PAG41") (pintype "bidirectional"))
    )
    (net (code "140") (name "unconnected-(U$1-AP_GPB18-PadPAG42)") (class "Default")
      (node (ref "U$1") (pin "PAG42") (pinfunction "AP_GPB18_PAG42") (pintype "bidirectional"))
    )
    (net (code "141") (name "unconnected-(U$1-AP_GPB23-PadPAL38)") (class "Default")
      (node (ref "U$1") (pin "PAL38") (pinfunction "AP_GPB23_PAL38") (pintype "bidirectional"))
    )
    (net (code "142") (name "unconnected-(U$1-AP_GPB30-PadPP41)") (class "Default")
      (node (ref "U$1") (pin "PP41") (pinfunction "AP_GPB30_PP41") (pintype "bidirectional"))
    )
    (net (code "143") (name "unconnected-(U$1-AP_GPC17-PadPAK33)") (class "Default")
      (node (ref "U$1") (pin "PAK33") (pinfunction "AP_GPC17_PAK33") (pintype "bidirectional"))
    )
    (net (code "144") (name "unconnected-(U$1-AP_GPC26-PadPAK35)") (class "Default")
      (node (ref "U$1") (pin "PAK35") (pinfunction "AP_GPC26_PAK35") (pintype "bidirectional"))
    )
    (net (code "145") (name "unconnected-(U$1-AP_GPD28-PadPAK19)") (class "Default")
      (node (ref "U$1") (pin "PAK19") (pinfunction "AP_GPD28_PAK19") (pintype "bidirectional"))
    )
    (net (code "146") (name "unconnected-(U$1-AP_GPD31-PadPAL25)") (class "Default")
      (node (ref "U$1") (pin "PAL25") (pinfunction "AP_GPD31_PAL25") (pintype "bidirectional"))
    )
    (net (code "147") (name "unconnected-(U$1-AP_GPE3-PadPAL20)") (class "Default")
      (node (ref "U$1") (pin "PAL20") (pinfunction "AP_GPE3_PAL20") (pintype "bidirectional"))
    )
    (net (code "148") (name "unconnected-(U$1-AP_HSIC_DATA-PadPB38)") (class "Default")
      (node (ref "U$1") (pin "PB38") (pinfunction "AP_HSIC_DATA_PB38") (pintype "bidirectional"))
    )
    (net (code "149") (name "unconnected-(U$1-AP_HSIC_STROBE-PadPA38)") (class "Default")
      (node (ref "U$1") (pin "PA38") (pinfunction "AP_HSIC_STROBE_PA38") (pintype "bidirectional"))
    )
    (net (code "150") (name "unconnected-(U$1-AP_LVDS_TN0-PadPA22)") (class "Default")
      (node (ref "U$1") (pin "PA22") (pinfunction "AP_LVDS_TN0_PA22") (pintype "bidirectional"))
    )
    (net (code "151") (name "unconnected-(U$1-AP_LVDS_TN1-PadPA23)") (class "Default")
      (node (ref "U$1") (pin "PA23") (pinfunction "AP_LVDS_TN1_PA23") (pintype "bidirectional"))
    )
    (net (code "152") (name "unconnected-(U$1-AP_LVDS_TN2-PadPA24)") (class "Default")
      (node (ref "U$1") (pin "PA24") (pinfunction "AP_LVDS_TN2_PA24") (pintype "bidirectional"))
    )
    (net (code "153") (name "unconnected-(U$1-AP_LVDS_TN3-PadPA26)") (class "Default")
      (node (ref "U$1") (pin "PA26") (pinfunction "AP_LVDS_TN3_PA26") (pintype "bidirectional"))
    )
    (net (code "154") (name "unconnected-(U$1-AP_LVDS_TN4-PadPA27)") (class "Default")
      (node (ref "U$1") (pin "PA27") (pinfunction "AP_LVDS_TN4_PA27") (pintype "bidirectional"))
    )
    (net (code "155") (name "unconnected-(U$1-AP_LVDS_TNCLK-PadPA25)") (class "Default")
      (node (ref "U$1") (pin "PA25") (pinfunction "AP_LVDS_TNCLK_PA25") (pintype "bidirectional"))
    )
    (net (code "156") (name "unconnected-(U$1-AP_LVDS_TP0-PadPB22)") (class "Default")
      (node (ref "U$1") (pin "PB22") (pinfunction "AP_LVDS_TP0_PB22") (pintype "bidirectional"))
    )
    (net (code "157") (name "unconnected-(U$1-AP_LVDS_TP1-PadPB23)") (class "Default")
      (node (ref "U$1") (pin "PB23") (pinfunction "AP_LVDS_TP1_PB23") (pintype "bidirectional"))
    )
    (net (code "158") (name "unconnected-(U$1-AP_LVDS_TP2-PadPB24)") (class "Default")
      (node (ref "U$1") (pin "PB24") (pinfunction "AP_LVDS_TP2_PB24") (pintype "bidirectional"))
    )
    (net (code "159") (name "unconnected-(U$1-AP_LVDS_TP3-PadPB26)") (class "Default")
      (node (ref "U$1") (pin "PB26") (pinfunction "AP_LVDS_TP3_PB26") (pintype "bidirectional"))
    )
    (net (code "160") (name "unconnected-(U$1-AP_LVDS_TP4-PadPB27)") (class "Default")
      (node (ref "U$1") (pin "PB27") (pinfunction "AP_LVDS_TP4_PB27") (pintype "bidirectional"))
    )
    (net (code "161") (name "unconnected-(U$1-AP_LVDS_TPCLK-PadPB25)") (class "Default")
      (node (ref "U$1") (pin "PB25") (pinfunction "AP_LVDS_TPCLK_PB25") (pintype "bidirectional"))
    )
    (net (code "162") (name "unconnected-(U$1-AP_NTRST-PadPAE1)") (class "Default")
      (node (ref "U$1") (pin "PAE1") (pinfunction "AP_NTRST_PAE1") (pintype "bidirectional"))
    )
    (net (code "163") (name "unconnected-(U$1-AP_SPI0_CLK-PadPAK6)") (class "Default")
      (node (ref "U$1") (pin "PAK6") (pinfunction "AP_SPI0_CLK_PAK6") (pintype "bidirectional"))
    )
    (net (code "164") (name "unconnected-(U$1-AP_SPI0_CS-PadPAL6)") (class "Default")
      (node (ref "U$1") (pin "PAL6") (pinfunction "AP_SPI0_CS_PAL6") (pintype "bidirectional"))
    )
    (net (code "165") (name "unconnected-(U$1-AP_SPI0_MISO-PadPAK5)") (class "Default")
      (node (ref "U$1") (pin "PAK5") (pinfunction "AP_SPI0_MISO_PAK5") (pintype "bidirectional"))
    )
    (net (code "166") (name "unconnected-(U$1-AP_SPI0_MOSI-PadPAL5)") (class "Default")
      (node (ref "U$1") (pin "PAL5") (pinfunction "AP_SPI0_MOSI_PAL5") (pintype "bidirectional"))
    )
    (net (code "167") (name "unconnected-(U$1-AP_TCK-PadPAC1)") (class "Default")
      (node (ref "U$1") (pin "PAC1") (pinfunction "AP_TCK_PAC1") (pintype "bidirectional"))
    )
    (net (code "168") (name "unconnected-(U$1-AP_TDI-PadPAD2)") (class "Default")
      (node (ref "U$1") (pin "PAD2") (pinfunction "AP_TDI_PAD2") (pintype "bidirectional"))
    )
    (net (code "169") (name "unconnected-(U$1-AP_TDO-PadPAD1)") (class "Default")
      (node (ref "U$1") (pin "PAD1") (pinfunction "AP_TDO_PAD1") (pintype "bidirectional"))
    )
    (net (code "170") (name "unconnected-(U$1-AP_TMS-PadPAC2)") (class "Default")
      (node (ref "U$1") (pin "PAC2") (pinfunction "AP_TMS_PAC2") (pintype "bidirectional"))
    )
    (net (code "171") (name "unconnected-(U$1-BT_PCM_CLK-PadPAJ39)") (class "Default")
      (node (ref "U$1") (pin "PAJ39") (pinfunction "BT_PCM_CLK_PAJ39") (pintype "bidirectional"))
    )
    (net (code "172") (name "unconnected-(U$1-BT_PCM_D_IN-PadPAJ40)") (class "Default")
      (node (ref "U$1") (pin "PAJ40") (pinfunction "BT_PCM_D_IN_PAJ40") (pintype "bidirectional"))
    )
    (net (code "173") (name "unconnected-(U$1-BT_PCM_D_OUT-PadPAJ41)") (class "Default")
      (node (ref "U$1") (pin "PAJ41") (pinfunction "BT_PCM_D_OUT_PAJ41") (pintype "bidirectional"))
    )
    (net (code "174") (name "unconnected-(U$1-BT_PCM_LRCK-PadPAJ42)") (class "Default")
      (node (ref "U$1") (pin "PAJ42") (pinfunction "BT_PCM_LRCK_PAJ42") (pintype "bidirectional"))
    )
    (net (code "175") (name "unconnected-(U$1-COMBO_ZIG_UART_RXD-PadPAL15)") (class "Default")
      (node (ref "U$1") (pin "PAL15") (pinfunction "COMBO_ZIG_UART_RXD_PAL15") (pintype "bidirectional"))
    )
    (net (code "176") (name "unconnected-(U$1-COMBO_ZIG_UART_TXD-PadPAK15)") (class "Default")
      (node (ref "U$1") (pin "PAK15") (pinfunction "COMBO_ZIG_UART_TXD_PAK15") (pintype "bidirectional"))
    )
    (net (code "177") (name "unconnected-(U$1-GMAC_GTXCLK-PadPA5)") (class "Default")
      (node (ref "U$1") (pin "PA5") (pinfunction "GMAC_GTXCLK_PA5") (pintype "bidirectional"))
    )
    (net (code "178") (name "unconnected-(U$1-GMAC_MDC-PadPB4)") (class "Default")
      (node (ref "U$1") (pin "PB4") (pinfunction "GMAC_MDC_PB4") (pintype "bidirectional"))
    )
    (net (code "179") (name "unconnected-(U$1-GMAC_MDIO-PadPB8)") (class "Default")
      (node (ref "U$1") (pin "PB8") (pinfunction "GMAC_MDIO_PB8") (pintype "bidirectional"))
    )
    (net (code "180") (name "unconnected-(U$1-GMAC_RXCLK-PadPB5)") (class "Default")
      (node (ref "U$1") (pin "PB5") (pinfunction "GMAC_RXCLK_PB5") (pintype "bidirectional"))
    )
    (net (code "181") (name "unconnected-(U$1-GMAC_RXD0-PadPA8)") (class "Default")
      (node (ref "U$1") (pin "PA8") (pinfunction "GMAC_RXD0_PA8") (pintype "bidirectional"))
    )
    (net (code "182") (name "unconnected-(U$1-GMAC_RXD1-PadPB7)") (class "Default")
      (node (ref "U$1") (pin "PB7") (pinfunction "GMAC_RXD1_PB7") (pintype "bidirectional"))
    )
    (net (code "183") (name "unconnected-(U$1-GMAC_RXD2-PadPA7)") (class "Default")
      (node (ref "U$1") (pin "PA7") (pinfunction "GMAC_RXD2_PA7") (pintype "bidirectional"))
    )
    (net (code "184") (name "unconnected-(U$1-GMAC_RXD3-PadPB6)") (class "Default")
      (node (ref "U$1") (pin "PB6") (pinfunction "GMAC_RXD3_PB6") (pintype "bidirectional"))
    )
    (net (code "185") (name "unconnected-(U$1-GMAC_RXDV-PadPA6)") (class "Default")
      (node (ref "U$1") (pin "PA6") (pinfunction "GMAC_RXDV_PA6") (pintype "bidirectional"))
    )
    (net (code "186") (name "unconnected-(U$1-GMAC_TXD0-PadPB2)") (class "Default")
      (node (ref "U$1") (pin "PB2") (pinfunction "GMAC_TXD0_PB2") (pintype "bidirectional"))
    )
    (net (code "187") (name "unconnected-(U$1-GMAC_TXD1-PadPA2)") (class "Default")
      (node (ref "U$1") (pin "PA2") (pinfunction "GMAC_TXD1_PA2") (pintype "bidirectional"))
    )
    (net (code "188") (name "unconnected-(U$1-GMAC_TXD2-PadPB3)") (class "Default")
      (node (ref "U$1") (pin "PB3") (pinfunction "GMAC_TXD2_PB3") (pintype "bidirectional"))
    )
    (net (code "189") (name "unconnected-(U$1-GMAC_TXD3-PadPA3)") (class "Default")
      (node (ref "U$1") (pin "PA3") (pinfunction "GMAC_TXD3_PA3") (pintype "bidirectional"))
    )
    (net (code "190") (name "unconnected-(U$1-GMAC_TXEN-PadPA1)") (class "Default")
      (node (ref "U$1") (pin "PA1") (pinfunction "GMAC_TXEN_PA1") (pintype "bidirectional"))
    )
    (net (code "191") (name "unconnected-(U$1-NC1-PadPAK31)") (class "Default")
      (node (ref "U$1") (pin "PAK31") (pinfunction "NC1_PAK31") (pintype "bidirectional"))
    )
    (net (code "192") (name "unconnected-(U$1-NC2-PadPAD41)") (class "Default")
      (node (ref "U$1") (pin "PAD41") (pinfunction "NC2_PAD41") (pintype "bidirectional"))
    )
    (net (code "193") (name "unconnected-(U$1-NC3-PadPAD42)") (class "Default")
      (node (ref "U$1") (pin "PAD42") (pinfunction "NC3_PAD42") (pintype "bidirectional"))
    )
    (net (code "194") (name "unconnected-(U$1-NC4-PadPAE42)") (class "Default")
      (node (ref "U$1") (pin "PAE42") (pinfunction "NC4_PAE42") (pintype "bidirectional"))
    )
    (net (code "195") (name "unconnected-(U$1-NC5-PadPE41)") (class "Default")
      (node (ref "U$1") (pin "PE41") (pinfunction "NC5_PE41") (pintype "bidirectional"))
    )
    (net (code "196") (name "unconnected-(U$1-NC6-PadPE42)") (class "Default")
      (node (ref "U$1") (pin "PE42") (pinfunction "NC6_PE42") (pintype "bidirectional"))
    )
    (net (code "197") (name "unconnected-(U$1-NC7-PadPF41)") (class "Default")
      (node (ref "U$1") (pin "PF41") (pinfunction "NC7_PF41") (pintype "bidirectional"))
    )
    (net (code "198") (name "unconnected-(U$1-NC8-PadPH41)") (class "Default")
      (node (ref "U$1") (pin "PH41") (pinfunction "NC8_PH41") (pintype "bidirectional"))
    )
    (net (code "199") (name "unconnected-(U$1-NC9-PadPH42)") (class "Default")
      (node (ref "U$1") (pin "PH42") (pinfunction "NC9_PH42") (pintype "bidirectional"))
    )
    (net (code "200") (name "unconnected-(U$1-NC10-PadPJ41)") (class "Default")
      (node (ref "U$1") (pin "PJ41") (pinfunction "NC10_PJ41") (pintype "bidirectional"))
    )
    (net (code "201") (name "unconnected-(U$1-NC11-PadPR41)") (class "Default")
      (node (ref "U$1") (pin "PR41") (pinfunction "NC11_PR41") (pintype "bidirectional"))
    )
    (net (code "202") (name "unconnected-(U$1-NC12-PadPR42)") (class "Default")
      (node (ref "U$1") (pin "PR42") (pinfunction "NC12_PR42") (pintype "bidirectional"))
    )
    (net (code "203") (name "unconnected-(U$1-PAD_ZB_RSTN-PadPAL14)") (class "Default")
      (node (ref "U$1") (pin "PAL14") (pinfunction "PAD_ZB_RSTN_PAL14") (pintype "bidirectional"))
    )
    (net (code "204") (name "unconnected-(U$1-ZB_DEBUG_TCK_SWCLK-PadPAK14)") (class "Default")
      (node (ref "U$1") (pin "PAK14") (pinfunction "ZB_DEBUG_TCK_SWCLK_PAK14") (pintype "bidirectional"))
    )
    (net (code "205") (name "unconnected-(U$1-ZB_DEBUG_TDO_SWO-PadPAK12)") (class "Default")
      (node (ref "U$1") (pin "PAK12") (pinfunction "ZB_DEBUG_TDO_SWO_PAK12") (pintype "bidirectional"))
    )
    (net (code "206") (name "unconnected-(U$1-ZB_DEBUG_TMS_SWDIO-PadPAL12)") (class "Default")
      (node (ref "U$1") (pin "PAL12") (pinfunction "ZB_DEBUG_TMS_SWDIO_PAL12") (pintype "bidirectional"))
    )
    (net (code "207") (name "unconnected-(U$1-ZB_PTI_DATA_FRC_DOUT-PadPAK13)") (class "Default")
      (node (ref "U$1") (pin "PAK13") (pinfunction "ZB_PTI_DATA_FRC_DOUT_PAK13") (pintype "bidirectional"))
    )
    (net (code "208") (name "unconnected-(U$1-ZB_PTI_SYNC_FRC_DFRAME-PadPAL13)") (class "Default")
      (node (ref "U$1") (pin "PAL13") (pinfunction "ZB_PTI_SYNC_FRC_DFRAME_PAL13") (pintype "bidirectional"))
    )
  )
)
